# design.net
KiCad netlist of a schematic drawn in EAGLE
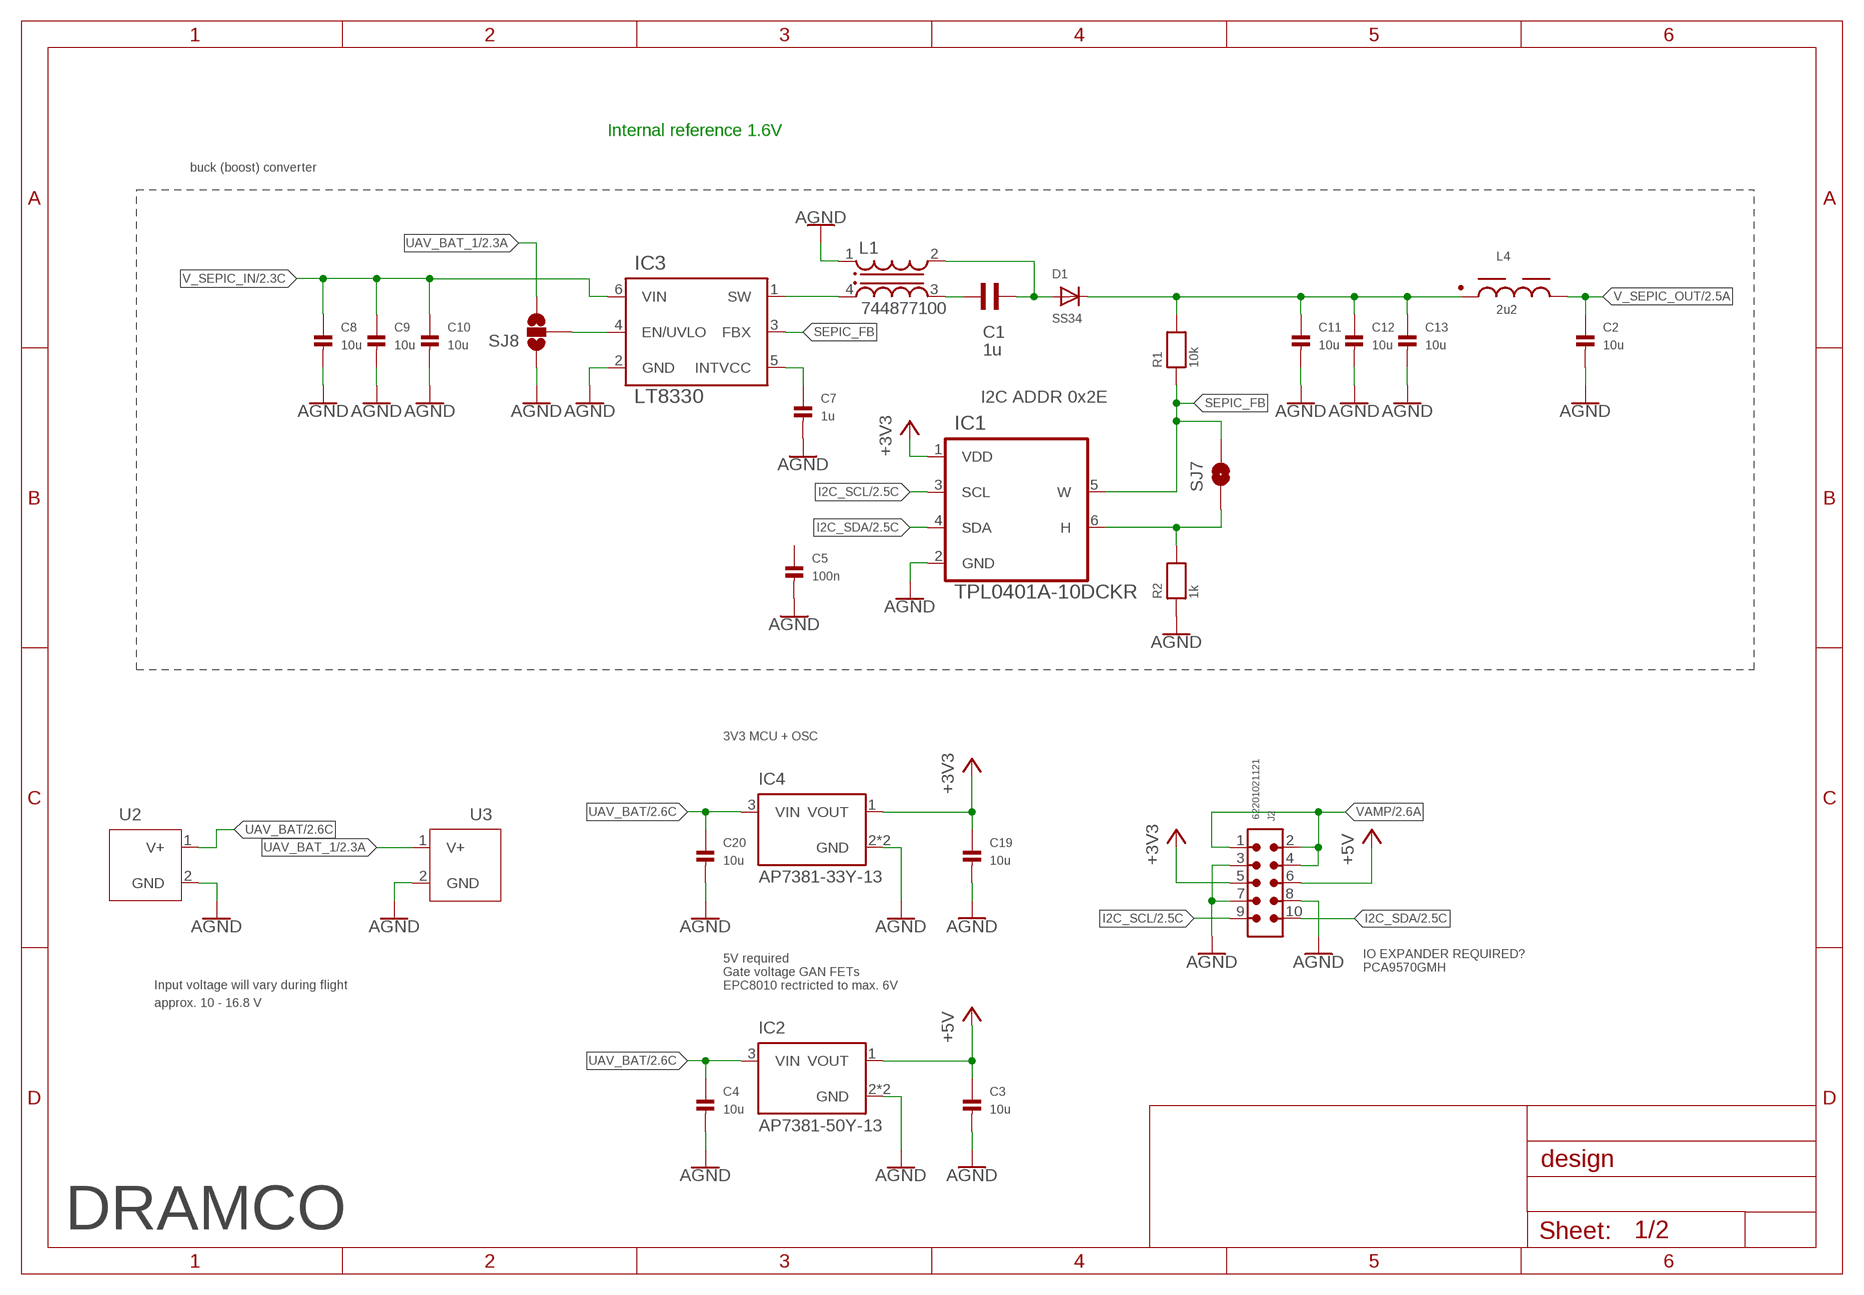
[diagram p0: schematic, sheet 1]
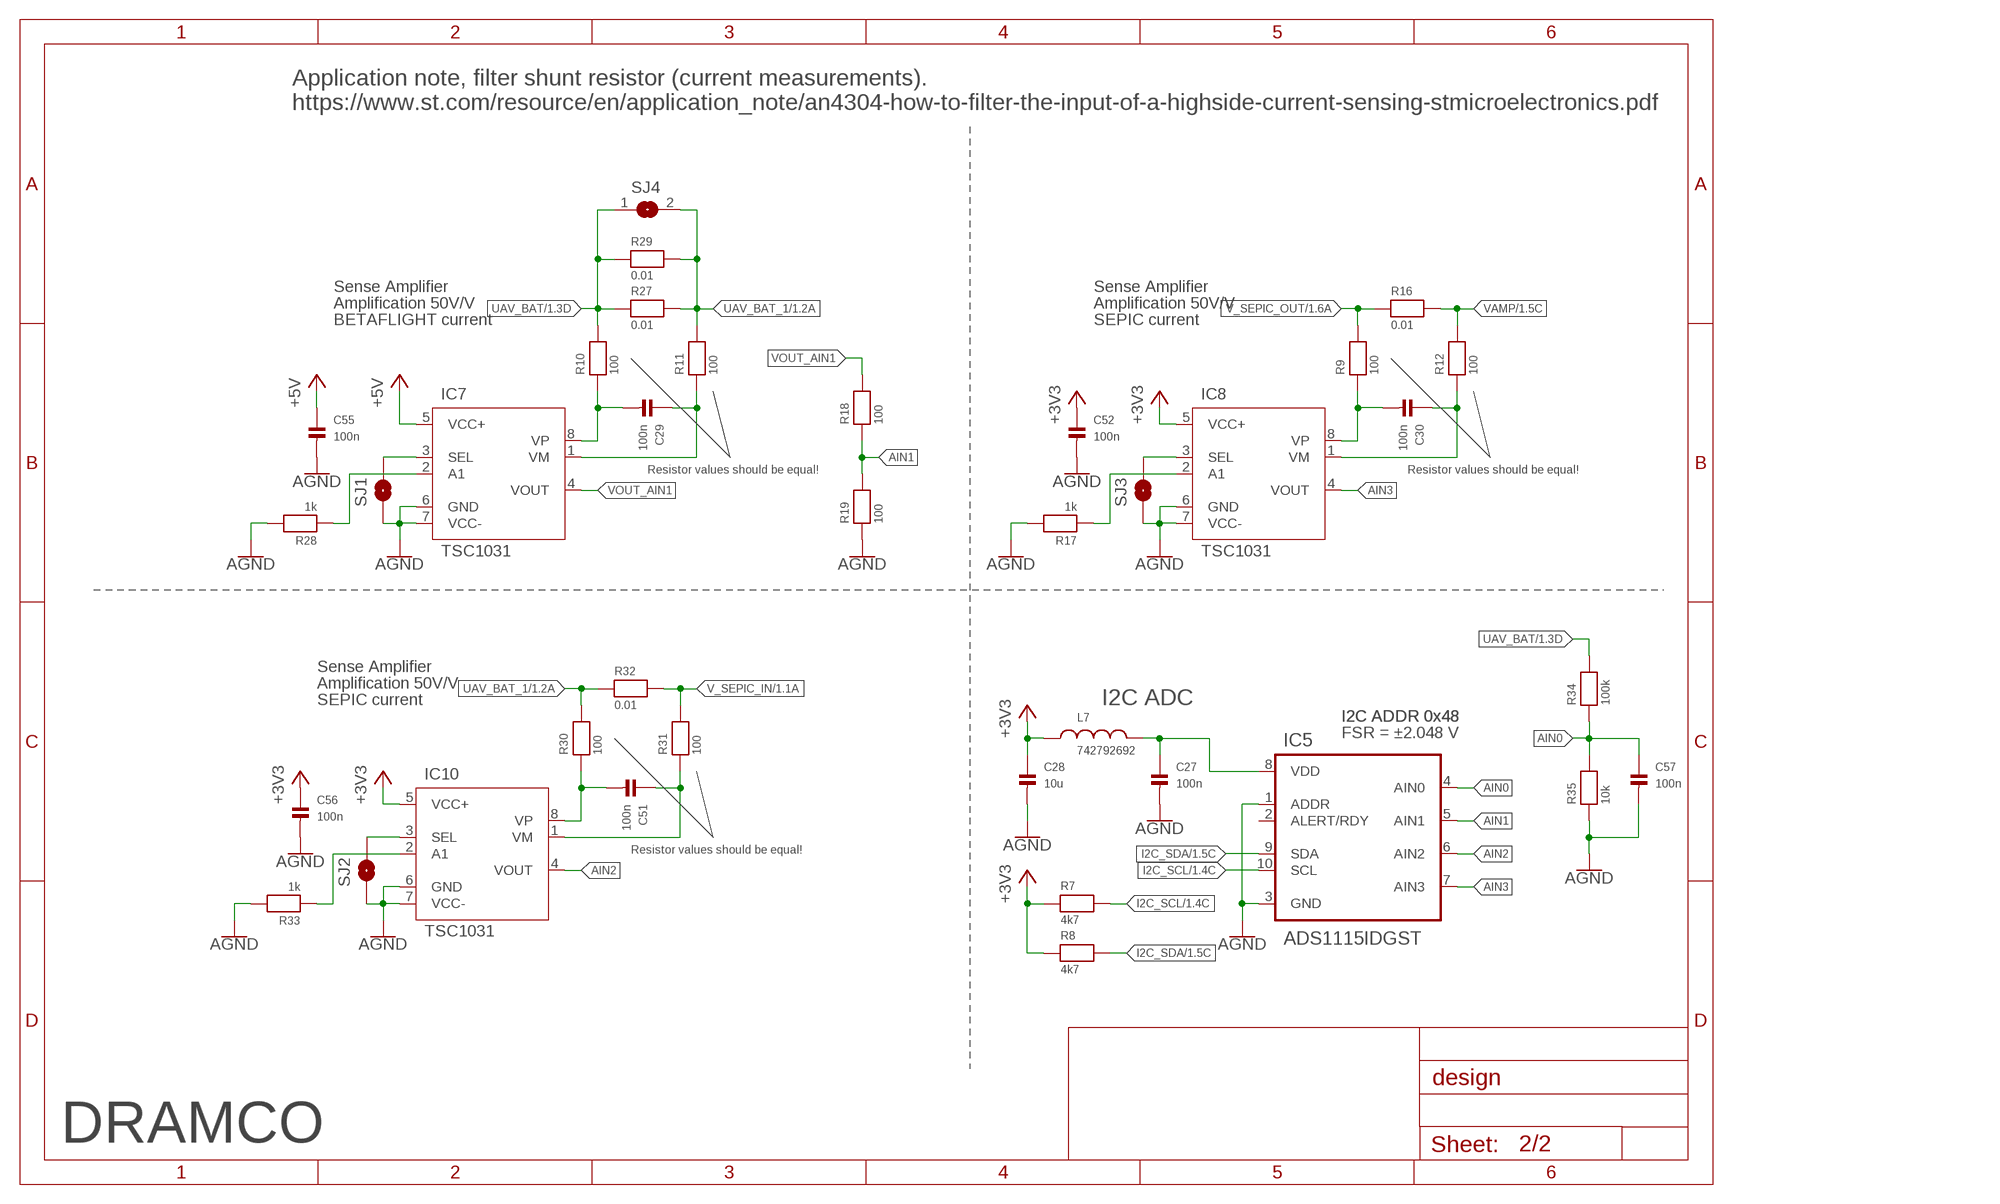
[diagram p1: schematic, sheet 2]

(export (version "E")
  (design (tool "Eeschema 10.0.6"))
  (components
    (comp (ref "C1")
      (value "1u")
      (footprint "eagle-import:WCAP-CSGP_0805_WAVE")
      (libsource (lib "eagle-import") (part "WCAP-CSGP_0805_WAVE_885012207103"))
    )
    (comp (ref "C2")
      (value "10u")
      (footprint "eagle-import:0805")
      (libsource (lib "eagle-import") (part "CAP_CERAMIC0805"))
    )
    (comp (ref "C3")
      (value "10u")
      (footprint "eagle-import:0603")
      (libsource (lib "eagle-import") (part "CAP_CERAMIC0603"))
    )
    (comp (ref "C4")
      (value "10u")
      (footprint "eagle-import:0603")
      (libsource (lib "eagle-import") (part "CAP_CERAMIC0603"))
    )
    (comp (ref "C5")
      (value "100n")
      (footprint "eagle-import:0402")
      (libsource (lib "eagle-import") (part "CAP_CERAMIC0402"))
    )
    (comp (ref "C7")
      (value "1u")
      (footprint "eagle-import:0603")
      (libsource (lib "eagle-import") (part "CAP_CERAMIC0603"))
    )
    (comp (ref "C8")
      (value "10u")
      (footprint "eagle-import:1206")
      (libsource (lib "eagle-import") (part "CAP_CERAMIC1206"))
    )
    (comp (ref "C9")
      (value "10u")
      (footprint "eagle-import:1206")
      (libsource (lib "eagle-import") (part "CAP_CERAMIC1206"))
    )
    (comp (ref "C10")
      (value "10u")
      (footprint "eagle-import:1206")
      (libsource (lib "eagle-import") (part "CAP_CERAMIC1206"))
    )
    (comp (ref "C11")
      (value "10u")
      (footprint "eagle-import:1206")
      (libsource (lib "eagle-import") (part "CAP_CERAMIC1206"))
    )
    (comp (ref "C12")
      (value "10u")
      (footprint "eagle-import:1206")
      (libsource (lib "eagle-import") (part "CAP_CERAMIC1206"))
    )
    (comp (ref "C13")
      (value "10u")
      (footprint "eagle-import:1206")
      (libsource (lib "eagle-import") (part "CAP_CERAMIC1206"))
    )
    (comp (ref "C19")
      (value "10u")
      (footprint "eagle-import:0603")
      (libsource (lib "eagle-import") (part "CAP_CERAMIC0603"))
    )
    (comp (ref "C20")
      (value "10u")
      (footprint "eagle-import:0603")
      (libsource (lib "eagle-import") (part "CAP_CERAMIC0603"))
    )
    (comp (ref "D1")
      (value "SS34")
      (footprint "eagle-import:SOD-123")
      (libsource (lib "eagle-import") (part "DIODESOD-123"))
    )
    (comp (ref "IC1")
      (value "TPL0401A-10DCKR")
      (footprint "eagle-import:SOT65P210X110-6N")
      (fields (field (name "MF") "Texas Instruments"))
      (libsource (lib "eagle-import") (part "TPL0401A-10DCKR"))
    )
    (comp (ref "IC2")
      (value "AP7381-50Y-13")
      (footprint "eagle-import:FOOT_XC6201P332PR-G")
      (fields (field (name "MF") "Microchip") (field (name "MP") "MCP1700T-3602E/MB"))
      (libsource (lib "eagle-import") (part "AP7381-50Y-13"))
    )
    (comp (ref "IC3")
      (value "LT8330")
      (footprint "eagle-import:TSOT-23_S6")
      (fields (field (name "MF") "Analog Devices") (field (name "MP") "LT8330ES6#TR"))
      (libsource (lib "eagle-import") (part "LT8330ES6TR"))
    )
    (comp (ref "IC4")
      (value "AP7381-33Y-13")
      (footprint "eagle-import:FOOT_XC6201P332PR-G")
      (fields (field (name "MF") "Microchip") (field (name "MP") "MCP1700T-3602E/MB"))
      (libsource (lib "eagle-import") (part "AP7381-50Y-13"))
    )
    (comp (ref "J2")
      (value "62201021121")
      (footprint "eagle-import:62201021121")
      (libsource (lib "eagle-import") (part "6220XX21121_62201021121"))
    )
    (comp (ref "L1")
      (value "744877100")
      (footprint "eagle-import:WE-DD_7345")
      (libsource (lib "eagle-import") (part "WE-DD_7345_744877100"))
    )
    (comp (ref "L4")
      (value "2u2")
      (footprint "eagle-import:WE-LQS_3015")
      (libsource (lib "eagle-import") (part "WE-LQS_3015_74404032022"))
    )
    (comp (ref "R1")
      (value "10k")
      (footprint "eagle-import:0603")
      (libsource (lib "eagle-import") (part "RESISTOR0603"))
    )
    (comp (ref "R2")
      (value "1k")
      (footprint "eagle-import:0603")
      (libsource (lib "eagle-import") (part "RESISTOR0603"))
    )
    (comp (ref "SJ7")
      (value "SOLDERJUMPERNO")
      (footprint "eagle-import:SJ_2S-NO")
      (libsource (lib "eagle-import") (part "SOLDERJUMPERNO"))
    )
    (comp (ref "SJ8")
      (value "SOLDERJUMPER_2WAYS")
      (footprint "eagle-import:SJ_3")
      (libsource (lib "eagle-import") (part "SOLDERJUMPER_2WAYS"))
    )
    (comp (ref "U2")
      (value "UAV-CONNECT")
      (footprint "eagle-import:HOLE")
      (libsource (lib "eagle-import") (part "UAV-CONNECT"))
    )
    (comp (ref "U3")
      (value "UAV-CONNECT")
      (footprint "eagle-import:HOLE")
      (libsource (lib "eagle-import") (part "UAV-CONNECT"))
    )
    (comp (ref "C27")
      (value "100n")
      (footprint "eagle-import:0402")
      (libsource (lib "eagle-import") (part "CAP_CERAMIC0402"))
    )
    (comp (ref "C28")
      (value "10u")
      (footprint "eagle-import:0603")
      (libsource (lib "eagle-import") (part "CAP_CERAMIC0603"))
    )
    (comp (ref "C29")
      (value "100n")
      (footprint "eagle-import:0402")
      (libsource (lib "eagle-import") (part "CAP_CERAMIC0402"))
    )
    (comp (ref "C30")
      (value "100n")
      (footprint "eagle-import:0402")
      (libsource (lib "eagle-import") (part "CAP_CERAMIC0402"))
    )
    (comp (ref "C51")
      (value "100n")
      (footprint "eagle-import:0402")
      (libsource (lib "eagle-import") (part "CAP_CERAMIC0402"))
    )
    (comp (ref "C52")
      (value "100n")
      (footprint "eagle-import:0402")
      (libsource (lib "eagle-import") (part "CAP_CERAMIC0402"))
    )
    (comp (ref "C55")
      (value "100n")
      (footprint "eagle-import:0402")
      (libsource (lib "eagle-import") (part "CAP_CERAMIC0402"))
    )
    (comp (ref "C56")
      (value "100n")
      (footprint "eagle-import:0402")
      (libsource (lib "eagle-import") (part "CAP_CERAMIC0402"))
    )
    (comp (ref "C57")
      (value "100n")
      (footprint "eagle-import:0402")
      (libsource (lib "eagle-import") (part "CAP_CERAMIC0402"))
    )
    (comp (ref "IC5")
      (value "ADS1115IDGST")
      (footprint "eagle-import:SOP50P490X110-10N")
      (fields (field (name "MF") "Texas Instruments"))
      (libsource (lib "eagle-import") (part "ADS1115IDGST"))
    )
    (comp (ref "IC7")
      (value "TSC1031")
      (footprint "eagle-import:SOP65P640X120-8N")
      (libsource (lib "eagle-import") (part "TSC1031IPT"))
    )
    (comp (ref "IC8")
      (value "TSC1031")
      (footprint "eagle-import:SOP65P640X120-8N")
      (libsource (lib "eagle-import") (part "TSC1031IPT"))
    )
    (comp (ref "IC10")
      (value "TSC1031")
      (footprint "eagle-import:SOP65P640X120-8N")
      (libsource (lib "eagle-import") (part "TSC1031IPT"))
    )
    (comp (ref "L7")
      (value "742792692")
      (footprint "eagle-import:WE-CBF_0603(W=2.2)")
      (libsource (lib "eagle-import") (part "WE-CBF_0603_WB_HS_742792692"))
    )
    (comp (ref "R7")
      (value "4k7")
      (footprint "eagle-import:0603")
      (libsource (lib "eagle-import") (part "RESISTOR0603"))
    )
    (comp (ref "R8")
      (value "4k7")
      (footprint "eagle-import:0603")
      (libsource (lib "eagle-import") (part "RESISTOR0603"))
    )
    (comp (ref "R9")
      (value "100")
      (footprint "eagle-import:0402")
      (libsource (lib "eagle-import") (part "RESISTOR0402"))
    )
    (comp (ref "R10")
      (value "100")
      (footprint "eagle-import:0402")
      (libsource (lib "eagle-import") (part "RESISTOR0402"))
    )
    (comp (ref "R11")
      (value "100")
      (footprint "eagle-import:0402")
      (libsource (lib "eagle-import") (part "RESISTOR0402"))
    )
    (comp (ref "R12")
      (value "100")
      (footprint "eagle-import:0402")
      (libsource (lib "eagle-import") (part "RESISTOR0402"))
    )
    (comp (ref "R16")
      (value "0.01")
      (footprint "eagle-import:0805")
      (libsource (lib "eagle-import") (part "RESISTOR0805"))
    )
    (comp (ref "R17")
      (value "1k")
      (footprint "eagle-import:0402")
      (libsource (lib "eagle-import") (part "RESISTOR0402"))
    )
    (comp (ref "R18")
      (value "100")
      (footprint "eagle-import:0603")
      (libsource (lib "eagle-import") (part "RESISTOR0603"))
    )
    (comp (ref "R19")
      (value "100")
      (footprint "eagle-import:0603")
      (libsource (lib "eagle-import") (part "RESISTOR0603"))
    )
    (comp (ref "R27")
      (value "0.01")
      (footprint "eagle-import:0805")
      (libsource (lib "eagle-import") (part "RESISTOR0805"))
    )
    (comp (ref "R28")
      (value "1k")
      (footprint "eagle-import:0402")
      (libsource (lib "eagle-import") (part "RESISTOR0402"))
    )
    (comp (ref "R29")
      (value "0.01")
      (footprint "eagle-import:0805")
      (libsource (lib "eagle-import") (part "RESISTOR0805"))
    )
    (comp (ref "R30")
      (value "100")
      (footprint "eagle-import:0402")
      (libsource (lib "eagle-import") (part "RESISTOR0402"))
    )
    (comp (ref "R31")
      (value "100")
      (footprint "eagle-import:0402")
      (libsource (lib "eagle-import") (part "RESISTOR0402"))
    )
    (comp (ref "R32")
      (value "0.01")
      (footprint "eagle-import:0805")
      (libsource (lib "eagle-import") (part "RESISTOR0805"))
    )
    (comp (ref "R33")
      (value "1k")
      (footprint "eagle-import:0402")
      (libsource (lib "eagle-import") (part "RESISTOR0402"))
    )
    (comp (ref "R34")
      (value "100k")
      (footprint "eagle-import:0603")
      (libsource (lib "eagle-import") (part "RESISTOR0603"))
    )
    (comp (ref "R35")
      (value "10k")
      (footprint "eagle-import:0603")
      (libsource (lib "eagle-import") (part "RESISTOR0603"))
    )
    (comp (ref "SJ1")
      (value "SOLDERJUMPERTRACE")
      (footprint "eagle-import:SJ_2S-TRACE")
      (libsource (lib "eagle-import") (part "SOLDERJUMPERTRACE"))
    )
    (comp (ref "SJ2")
      (value "SOLDERJUMPERTRACE")
      (footprint "eagle-import:SJ_2S-TRACE")
      (libsource (lib "eagle-import") (part "SOLDERJUMPERTRACE"))
    )
    (comp (ref "SJ3")
      (value "SOLDERJUMPERTRACE")
      (footprint "eagle-import:SJ_2S-TRACE")
      (libsource (lib "eagle-import") (part "SOLDERJUMPERTRACE"))
    )
    (comp (ref "SJ4")
      (value "SOLDERJUMPERREFLOW")
      (footprint "eagle-import:SOLDERJUMPER_REFLOW")
      (libsource (lib "eagle-import") (part "SOLDERJUMPERREFLOW"))
    )
  )
  (nets
    (net (code "1") (name "+3V3") (class "Default")
      (node (ref "C19") (pin "1") (pinfunction "P$1_1") (pintype "passive"))
      (node (ref "C28") (pin "1") (pinfunction "P$1_1") (pintype "passive"))
      (node (ref "C52") (pin "1") (pinfunction "P$1_1") (pintype "passive"))
      (node (ref "C56") (pin "1") (pinfunction "P$1_1") (pintype "passive"))
      (node (ref "IC1") (pin "1") (pinfunction "VDD_1") (pintype "power_in"))
      (node (ref "IC10") (pin "5") (pinfunction "VCC+_5") (pintype "bidirectional"))
      (node (ref "IC4") (pin "1") (pinfunction "VOUT_1") (pintype "output"))
      (node (ref "IC8") (pin "5") (pinfunction "VCC+_5") (pintype "bidirectional"))
      (node (ref "J2") (pin "5") (pinfunction "5_5") (pintype "passive"))
      (node (ref "L7") (pin "1") (pinfunction "1_1") (pintype "passive"))
      (node (ref "R7") (pin "1") (pinfunction "1_1") (pintype "passive"))
      (node (ref "R8") (pin "1") (pinfunction "1_1") (pintype "passive"))
    )
    (net (code "2") (name "+5V") (class "Default")
      (node (ref "C3") (pin "1") (pinfunction "P$1_1") (pintype "passive"))
      (node (ref "C55") (pin "1") (pinfunction "P$1_1") (pintype "passive"))
      (node (ref "IC2") (pin "1") (pinfunction "VOUT_1") (pintype "output"))
      (node (ref "IC7") (pin "5") (pinfunction "VCC+_5") (pintype "bidirectional"))
      (node (ref "J2") (pin "6") (pinfunction "6_6") (pintype "passive"))
    )
    (net (code "3") (name "AGND") (class "Default")
      (node (ref "C10") (pin "2") (pinfunction "P$2_2") (pintype "passive"))
      (node (ref "C11") (pin "2") (pinfunction "P$2_2") (pintype "passive"))
      (node (ref "C12") (pin "2") (pinfunction "P$2_2") (pintype "passive"))
      (node (ref "C13") (pin "2") (pinfunction "P$2_2") (pintype "passive"))
      (node (ref "C19") (pin "2") (pinfunction "P$2_2") (pintype "passive"))
      (node (ref "C2") (pin "2") (pinfunction "P$2_2") (pintype "passive"))
      (node (ref "C20") (pin "2") (pinfunction "P$2_2") (pintype "passive"))
      (node (ref "C27") (pin "2") (pinfunction "P$2_2") (pintype "passive"))
      (node (ref "C28") (pin "2") (pinfunction "P$2_2") (pintype "passive"))
      (node (ref "C3") (pin "2") (pinfunction "P$2_2") (pintype "passive"))
      (node (ref "C4") (pin "2") (pinfunction "P$2_2") (pintype "passive"))
      (node (ref "C5") (pin "2") (pinfunction "P$2_2") (pintype "passive"))
      (node (ref "C52") (pin "2") (pinfunction "P$2_2") (pintype "passive"))
      (node (ref "C55") (pin "2") (pinfunction "P$2_2") (pintype "passive"))
      (node (ref "C56") (pin "2") (pinfunction "P$2_2") (pintype "passive"))
      (node (ref "C57") (pin "2") (pinfunction "P$2_2") (pintype "passive"))
      (node (ref "C7") (pin "2") (pinfunction "P$2_2") (pintype "passive"))
      (node (ref "C8") (pin "2") (pinfunction "P$2_2") (pintype "passive"))
      (node (ref "C9") (pin "2") (pinfunction "P$2_2") (pintype "passive"))
      (node (ref "IC1") (pin "2") (pinfunction "GND_2") (pintype "power_in"))
      (node (ref "IC10") (pin "6") (pinfunction "GND_6") (pintype "bidirectional"))
      (node (ref "IC10") (pin "7") (pinfunction "VCC-_7") (pintype "bidirectional"))
      (node (ref "IC2") (pin "2") (pinfunction "GND_2") (pintype "power_in"))
      (node (ref "IC2") (pin "2.1") (pinfunction "GND_2.1") (pintype "power_in"))
      (node (ref "IC3") (pin "2") (pinfunction "GND_2") (pintype "power_in"))
      (node (ref "IC4") (pin "2") (pinfunction "GND_2") (pintype "power_in"))
      (node (ref "IC4") (pin "2.1") (pinfunction "GND_2.1") (pintype "power_in"))
      (node (ref "IC5") (pin "1") (pinfunction "ADDR_1") (pintype "input"))
      (node (ref "IC5") (pin "3") (pinfunction "GND_3") (pintype "passive"))
      (node (ref "IC7") (pin "6") (pinfunction "GND_6") (pintype "bidirectional"))
      (node (ref "IC7") (pin "7") (pinfunction "VCC-_7") (pintype "bidirectional"))
      (node (ref "IC8") (pin "6") (pinfunction "GND_6") (pintype "bidirectional"))
      (node (ref "IC8") (pin "7") (pinfunction "VCC-_7") (pintype "bidirectional"))
      (node (ref "J2") (pin "3") (pinfunction "3_3") (pintype "passive"))
      (node (ref "J2") (pin "7") (pinfunction "7_7") (pintype "passive"))
      (node (ref "J2") (pin "8") (pinfunction "8_8") (pintype "passive"))
      (node (ref "L1") (pin "1") (pinfunction "1_1") (pintype "passive"))
      (node (ref "R17") (pin "2") (pinfunction "2_2") (pintype "passive"))
      (node (ref "R19") (pin "1") (pinfunction "1_1") (pintype "passive"))
      (node (ref "R2") (pin "1") (pinfunction "1_1") (pintype "passive"))
      (node (ref "R28") (pin "2") (pinfunction "2_2") (pintype "passive"))
      (node (ref "R33") (pin "2") (pinfunction "2_2") (pintype "passive"))
      (node (ref "R35") (pin "1") (pinfunction "1_1") (pintype "passive"))
      (node (ref "SJ1") (pin "1") (pinfunction "1_1") (pintype "passive"))
      (node (ref "SJ2") (pin "1") (pinfunction "1_1") (pintype "passive"))
      (node (ref "SJ3") (pin "1") (pinfunction "1_1") (pintype "passive"))
      (node (ref "SJ8") (pin "1") (pinfunction "1_1") (pintype "passive"))
      (node (ref "U2") (pin "2") (pinfunction "GND_2") (pintype "bidirectional"))
      (node (ref "U3") (pin "2") (pinfunction "GND_2") (pintype "bidirectional"))
    )
    (net (code "4") (name "AIN0") (class "Default")
      (node (ref "C57") (pin "1") (pinfunction "P$1_1") (pintype "passive"))
      (node (ref "IC5") (pin "4") (pinfunction "AIN0_4") (pintype "input"))
      (node (ref "R34") (pin "1") (pinfunction "1_1") (pintype "passive"))
      (node (ref "R35") (pin "2") (pinfunction "2_2") (pintype "passive"))
    )
    (net (code "5") (name "AIN1") (class "Default")
      (node (ref "IC5") (pin "5") (pinfunction "AIN1_5") (pintype "input"))
      (node (ref "R18") (pin "1") (pinfunction "1_1") (pintype "passive"))
      (node (ref "R19") (pin "2") (pinfunction "2_2") (pintype "passive"))
    )
    (net (code "6") (name "AIN2") (class "Default")
      (node (ref "IC10") (pin "4") (pinfunction "VOUT_4") (pintype "bidirectional"))
      (node (ref "IC5") (pin "6") (pinfunction "AIN2_6") (pintype "input"))
    )
    (net (code "7") (name "AIN3") (class "Default")
      (node (ref "IC5") (pin "7") (pinfunction "AIN3_7") (pintype "input"))
      (node (ref "IC8") (pin "4") (pinfunction "VOUT_4") (pintype "bidirectional"))
    )
    (net (code "8") (name "I2C_SCL") (class "Default")
      (node (ref "IC1") (pin "3") (pinfunction "SCL_3") (pintype "bidirectional"))
      (node (ref "IC5") (pin "10") (pinfunction "SCL_10") (pintype "input"))
      (node (ref "J2") (pin "9") (pinfunction "9_9") (pintype "passive"))
      (node (ref "R7") (pin "2") (pinfunction "2_2") (pintype "passive"))
    )
    (net (code "9") (name "I2C_SDA") (class "Default")
      (node (ref "IC1") (pin "4") (pinfunction "SDA_4") (pintype "bidirectional"))
      (node (ref "IC5") (pin "9") (pinfunction "SDA_9") (pintype "bidirectional"))
      (node (ref "J2") (pin "10") (pinfunction "10_10") (pintype "passive"))
      (node (ref "R8") (pin "2") (pinfunction "2_2") (pintype "passive"))
    )
    (net (code "10") (name "Net-(C1-Pad1)") (class "Default")
      (node (ref "C1") (pin "1") (pinfunction "1_1") (pintype "passive"))
      (node (ref "D1") (pin "A") (pinfunction "A_A") (pintype "passive"))
      (node (ref "L1") (pin "2") (pinfunction "2_2") (pintype "passive"))
    )
    (net (code "11") (name "Net-(C1-Pad2)") (class "Default")
      (node (ref "C1") (pin "2") (pinfunction "2_2") (pintype "passive"))
      (node (ref "L1") (pin "3") (pinfunction "3_3") (pintype "passive"))
    )
    (net (code "12") (name "Net-(C7-P$1)") (class "Default")
      (node (ref "C7") (pin "1") (pinfunction "P$1_1") (pintype "passive"))
      (node (ref "IC3") (pin "5") (pinfunction "INTVCC_5") (pintype "passive"))
    )
    (net (code "13") (name "Net-(C11-P$1)") (class "Default")
      (node (ref "C11") (pin "1") (pinfunction "P$1_1") (pintype "passive"))
      (node (ref "C12") (pin "1") (pinfunction "P$1_1") (pintype "passive"))
      (node (ref "C13") (pin "1") (pinfunction "P$1_1") (pintype "passive"))
      (node (ref "D1") (pin "C") (pinfunction "C_C") (pintype "passive"))
      (node (ref "L4") (pin "1") (pinfunction "1_1") (pintype "passive"))
      (node (ref "R1") (pin "2") (pinfunction "2_2") (pintype "passive"))
    )
    (net (code "14") (name "Net-(C27-P$1)") (class "Default")
      (node (ref "C27") (pin "1") (pinfunction "P$1_1") (pintype "passive"))
      (node (ref "IC5") (pin "8") (pinfunction "VDD_8") (pintype "power_in"))
      (node (ref "L7") (pin "2") (pinfunction "2_2") (pintype "passive"))
    )
    (net (code "15") (name "Net-(C29-P$1)") (class "Default")
      (node (ref "C29") (pin "1") (pinfunction "P$1_1") (pintype "passive"))
      (node (ref "IC7") (pin "1") (pinfunction "VM_1") (pintype "bidirectional"))
      (node (ref "R11") (pin "1") (pinfunction "1_1") (pintype "passive"))
    )
    (net (code "16") (name "Net-(C29-P$2)") (class "Default")
      (node (ref "C29") (pin "2") (pinfunction "P$2_2") (pintype "passive"))
      (node (ref "IC7") (pin "8") (pinfunction "VP_8") (pintype "bidirectional"))
      (node (ref "R10") (pin "1") (pinfunction "1_1") (pintype "passive"))
    )
    (net (code "17") (name "Net-(C30-P$1)") (class "Default")
      (node (ref "C30") (pin "1") (pinfunction "P$1_1") (pintype "passive"))
      (node (ref "IC8") (pin "1") (pinfunction "VM_1") (pintype "bidirectional"))
      (node (ref "R12") (pin "1") (pinfunction "1_1") (pintype "passive"))
    )
    (net (code "18") (name "Net-(C30-P$2)") (class "Default")
      (node (ref "C30") (pin "2") (pinfunction "P$2_2") (pintype "passive"))
      (node (ref "IC8") (pin "8") (pinfunction "VP_8") (pintype "bidirectional"))
      (node (ref "R9") (pin "1") (pinfunction "1_1") (pintype "passive"))
    )
    (net (code "19") (name "Net-(C51-P$1)") (class "Default")
      (node (ref "C51") (pin "1") (pinfunction "P$1_1") (pintype "passive"))
      (node (ref "IC10") (pin "1") (pinfunction "VM_1") (pintype "bidirectional"))
      (node (ref "R31") (pin "1") (pinfunction "1_1") (pintype "passive"))
    )
    (net (code "20") (name "Net-(C51-P$2)") (class "Default")
      (node (ref "C51") (pin "2") (pinfunction "P$2_2") (pintype "passive"))
      (node (ref "IC10") (pin "8") (pinfunction "VP_8") (pintype "bidirectional"))
      (node (ref "R30") (pin "1") (pinfunction "1_1") (pintype "passive"))
    )
    (net (code "21") (name "Net-(IC1-H)") (class "Default")
      (node (ref "IC1") (pin "6") (pinfunction "H_6") (pintype "bidirectional"))
      (node (ref "R2") (pin "2") (pinfunction "2_2") (pintype "passive"))
      (node (ref "SJ7") (pin "1") (pinfunction "1_1") (pintype "passive"))
    )
    (net (code "22") (name "Net-(IC3-EN{slash}UVLO)") (class "Default")
      (node (ref "IC3") (pin "4") (pinfunction "EN/UVLO_4") (pintype "passive"))
      (node (ref "SJ8") (pin "2") (pinfunction "2_2") (pintype "passive"))
    )
    (net (code "23") (name "Net-(IC3-SW)") (class "Default")
      (node (ref "IC3") (pin "1") (pinfunction "SW_1") (pintype "output"))
      (node (ref "L1") (pin "4") (pinfunction "4_4") (pintype "passive"))
    )
    (net (code "24") (name "Net-(IC7-A1)") (class "Default")
      (node (ref "IC7") (pin "2") (pinfunction "A1_2") (pintype "bidirectional"))
      (node (ref "R28") (pin "1") (pinfunction "1_1") (pintype "passive"))
    )
    (net (code "25") (name "Net-(IC7-SEL)") (class "Default")
      (node (ref "IC7") (pin "3") (pinfunction "SEL_3") (pintype "bidirectional"))
      (node (ref "SJ1") (pin "2") (pinfunction "2_2") (pintype "passive"))
    )
    (net (code "26") (name "Net-(IC8-A1)") (class "Default")
      (node (ref "IC8") (pin "2") (pinfunction "A1_2") (pintype "bidirectional"))
      (node (ref "R17") (pin "1") (pinfunction "1_1") (pintype "passive"))
    )
    (net (code "27") (name "Net-(IC8-SEL)") (class "Default")
      (node (ref "IC8") (pin "3") (pinfunction "SEL_3") (pintype "bidirectional"))
      (node (ref "SJ3") (pin "2") (pinfunction "2_2") (pintype "passive"))
    )
    (net (code "28") (name "Net-(IC10-A1)") (class "Default")
      (node (ref "IC10") (pin "2") (pinfunction "A1_2") (pintype "bidirectional"))
      (node (ref "R33") (pin "1") (pinfunction "1_1") (pintype "passive"))
    )
    (net (code "29") (name "Net-(IC10-SEL)") (class "Default")
      (node (ref "IC10") (pin "3") (pinfunction "SEL_3") (pintype "bidirectional"))
      (node (ref "SJ2") (pin "2") (pinfunction "2_2") (pintype "passive"))
    )
    (net (code "30") (name "SEPIC_FB") (class "Default")
      (node (ref "IC1") (pin "5") (pinfunction "W_5") (pintype "bidirectional"))
      (node (ref "IC3") (pin "3") (pinfunction "FBX_3") (pintype "output"))
      (node (ref "R1") (pin "1") (pinfunction "1_1") (pintype "passive"))
      (node (ref "SJ7") (pin "2") (pinfunction "2_2") (pintype "passive"))
    )
    (net (code "31") (name "UAV_BAT") (class "Default")
      (node (ref "C20") (pin "1") (pinfunction "P$1_1") (pintype "passive"))
      (node (ref "C4") (pin "1") (pinfunction "P$1_1") (pintype "passive"))
      (node (ref "IC2") (pin "3") (pinfunction "VIN_3") (pintype "input"))
      (node (ref "IC4") (pin "3") (pinfunction "VIN_3") (pintype "input"))
      (node (ref "R10") (pin "2") (pinfunction "2_2") (pintype "passive"))
      (node (ref "R27") (pin "1") (pinfunction "1_1") (pintype "passive"))
      (node (ref "R29") (pin "1") (pinfunction "1_1") (pintype "passive"))
      (node (ref "R34") (pin "2") (pinfunction "2_2") (pintype "passive"))
      (node (ref "SJ4") (pin "1") (pinfunction "1_1") (pintype "passive"))
      (node (ref "U2") (pin "1") (pinfunction "V+_1") (pintype "bidirectional"))
    )
    (net (code "32") (name "UAV_BAT_1") (class "Default")
      (node (ref "R11") (pin "2") (pinfunction "2_2") (pintype "passive"))
      (node (ref "R27") (pin "2") (pinfunction "2_2") (pintype "passive"))
      (node (ref "R29") (pin "2") (pinfunction "2_2") (pintype "passive"))
      (node (ref "R30") (pin "2") (pinfunction "2_2") (pintype "passive"))
      (node (ref "R32") (pin "1") (pinfunction "1_1") (pintype "passive"))
      (node (ref "SJ4") (pin "2") (pinfunction "2_2") (pintype "passive"))
      (node (ref "SJ8") (pin "3") (pinfunction "3_3") (pintype "passive"))
      (node (ref "U3") (pin "1") (pinfunction "V+_1") (pintype "bidirectional"))
    )
    (net (code "33") (name "VAMP") (class "Default")
      (node (ref "J2") (pin "1") (pinfunction "1_1") (pintype "passive"))
      (node (ref "J2") (pin "2") (pinfunction "2_2") (pintype "passive"))
      (node (ref "J2") (pin "4") (pinfunction "4_4") (pintype "passive"))
      (node (ref "R12") (pin "2") (pinfunction "2_2") (pintype "passive"))
      (node (ref "R16") (pin "2") (pinfunction "2_2") (pintype "passive"))
    )
    (net (code "34") (name "VOUT_AIN1") (class "Default")
      (node (ref "IC7") (pin "4") (pinfunction "VOUT_4") (pintype "bidirectional"))
      (node (ref "R18") (pin "2") (pinfunction "2_2") (pintype "passive"))
    )
    (net (code "35") (name "V_SEPIC_IN") (class "Default")
      (node (ref "C10") (pin "1") (pinfunction "P$1_1") (pintype "passive"))
      (node (ref "C8") (pin "1") (pinfunction "P$1_1") (pintype "passive"))
      (node (ref "C9") (pin "1") (pinfunction "P$1_1") (pintype "passive"))
      (node (ref "IC3") (pin "6") (pinfunction "VIN_6") (pintype "input"))
      (node (ref "R31") (pin "2") (pinfunction "2_2") (pintype "passive"))
      (node (ref "R32") (pin "2") (pinfunction "2_2") (pintype "passive"))
    )
    (net (code "36") (name "V_SEPIC_OUT") (class "Default")
      (node (ref "C2") (pin "1") (pinfunction "P$1_1") (pintype "passive"))
      (node (ref "L4") (pin "2") (pinfunction "2_2") (pintype "passive"))
      (node (ref "R16") (pin "1") (pinfunction "1_1") (pintype "passive"))
      (node (ref "R9") (pin "2") (pinfunction "2_2") (pintype "passive"))
    )
    (net (code "37") (name "unconnected-(C5-P$1-Pad1)") (class "Default")
      (node (ref "C5") (pin "1") (pinfunction "P$1_1") (pintype "passive"))
    )
    (net (code "38") (name "unconnected-(IC5-ALERT{slash}RDY-Pad2)") (class "Default")
      (node (ref "IC5") (pin "2") (pinfunction "ALERT/RDY_2") (pintype "input"))
    )
  )
)
